# darwin-water-temp-module.net
KiCad netlist of a schematic drawn in EAGLE
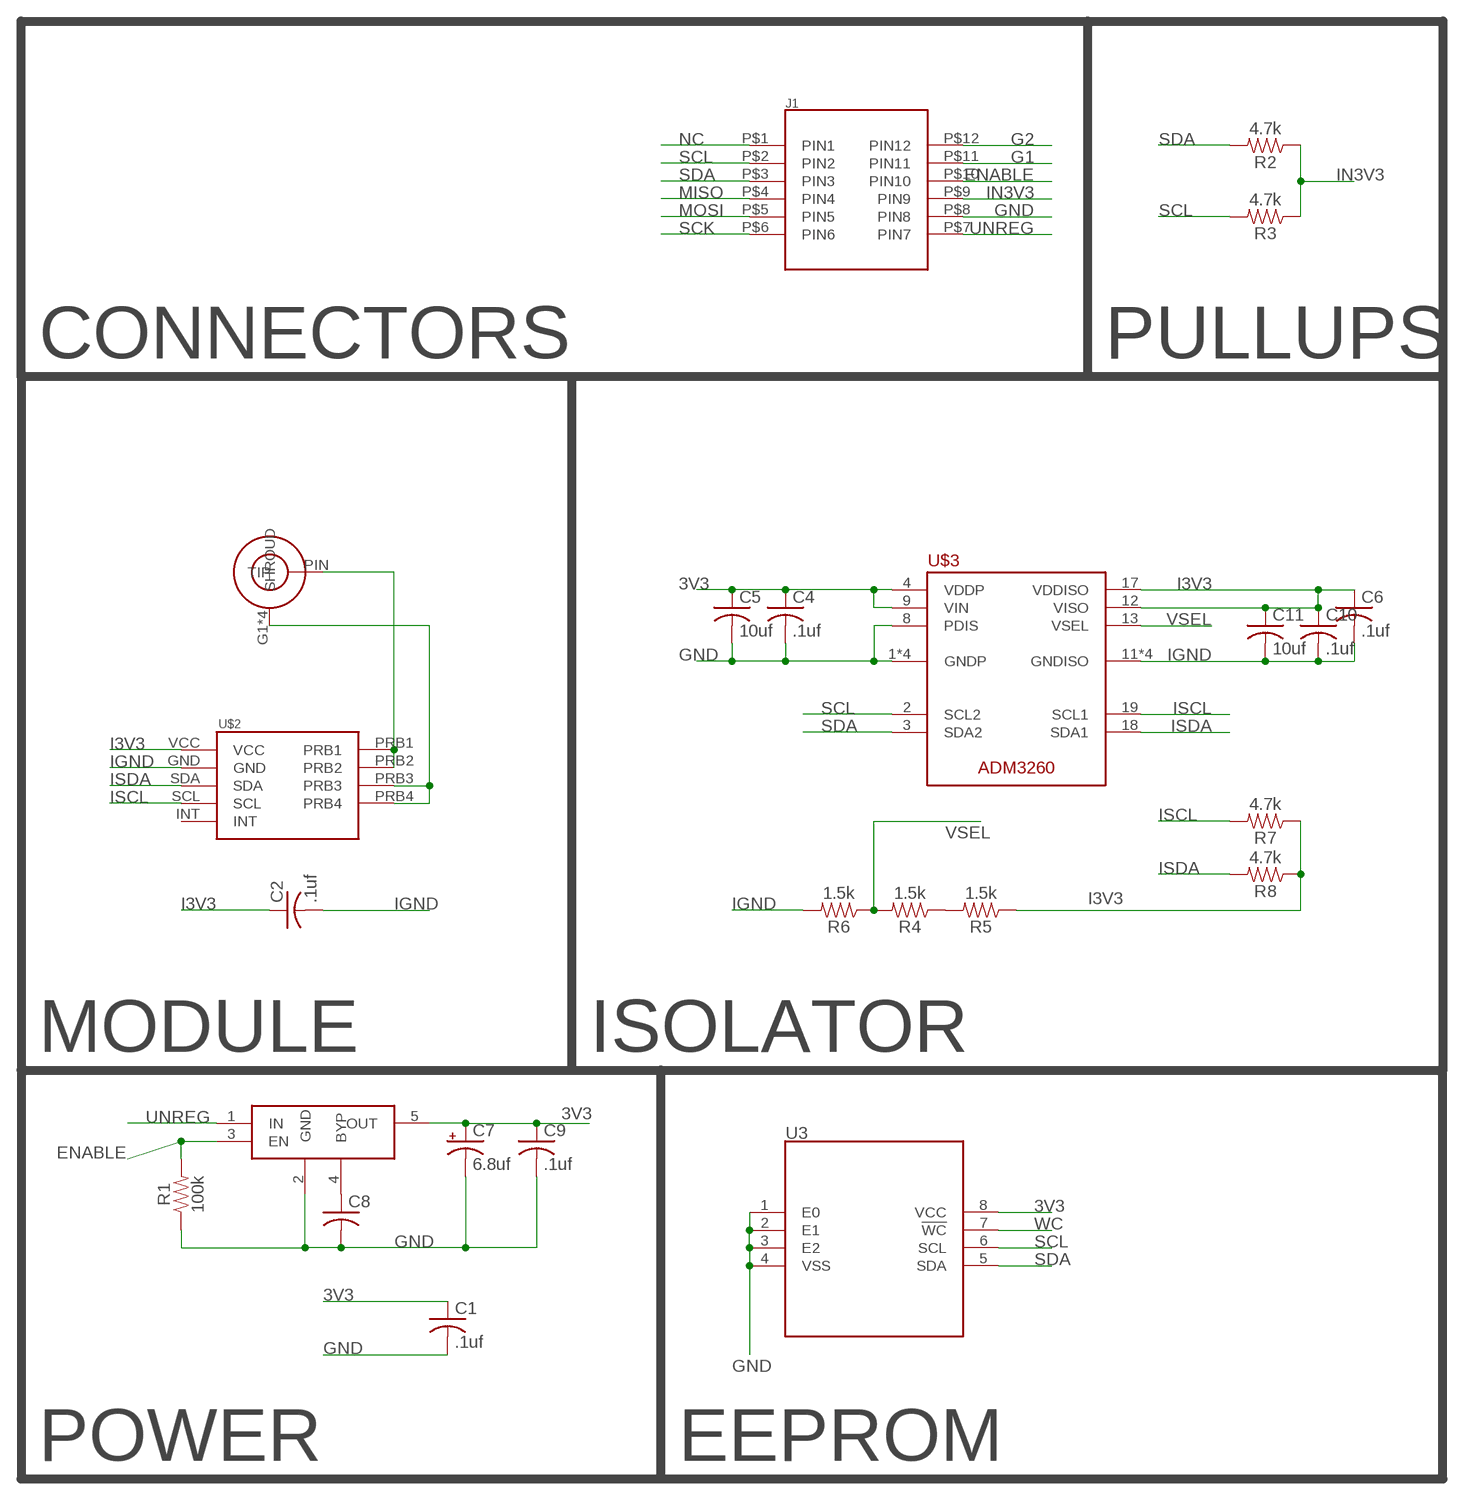
[diagram p0: schematic, sheet 1]

(export (version "E")
  (design (tool "Eeschema 10.0.6"))
  (components
    (comp (ref "C1")
      (value ".1uf")
      (footprint "eagle-import:C0603K")
      (libsource (lib "eagle-import") (part "C-USC0603K"))
    )
    (comp (ref "C2")
      (value ".1uf")
      (footprint "eagle-import:C0603K")
      (libsource (lib "eagle-import") (part "C-USC0603K"))
    )
    (comp (ref "C4")
      (value ".1uf")
      (footprint "eagle-import:C0603K")
      (libsource (lib "eagle-import") (part "C-USC0603K"))
    )
    (comp (ref "C5")
      (value "10uf")
      (footprint "eagle-import:C0603K")
      (libsource (lib "eagle-import") (part "C-USC0603K"))
    )
    (comp (ref "C6")
      (value ".1uf")
      (footprint "eagle-import:C0603K")
      (libsource (lib "eagle-import") (part "C-USC0603K"))
    )
    (comp (ref "C7")
      (value "6.8uf")
      (footprint "eagle-import:A_3216-18R")
      (libsource (lib "eagle-import") (part "CPOL-USA/3216-18R"))
    )
    (comp (ref "C8")
      (value "C-USC0603K")
      (footprint "eagle-import:C0603K")
      (libsource (lib "eagle-import") (part "C-USC0603K"))
    )
    (comp (ref "C9")
      (value ".1uf")
      (footprint "eagle-import:C0603K")
      (libsource (lib "eagle-import") (part "C-USC0603K"))
    )
    (comp (ref "C10")
      (value ".1uf")
      (footprint "eagle-import:C0603K")
      (libsource (lib "eagle-import") (part "C-USC0603K"))
    )
    (comp (ref "C11")
      (value "10uf")
      (footprint "eagle-import:C0603K")
      (libsource (lib "eagle-import") (part "C-USC0603K"))
    )
    (comp (ref "J1")
      (value "2X6-HEADERS")
      (footprint "eagle-import:M20-7810645")
      (libsource (lib "eagle-import") (part "2X6-HEADERS"))
    )
    (comp (ref "R1")
      (value "100k")
      (footprint "eagle-import:0603")
      (libsource (lib "eagle-import") (part "100KOHM-0603-1/10W-1%"))
    )
    (comp (ref "R2")
      (value "4.7k")
      (footprint "eagle-import:0603")
      (libsource (lib "eagle-import") (part "100KOHM-0603-1/10W-1%"))
    )
    (comp (ref "R3")
      (value "4.7k")
      (footprint "eagle-import:0603")
      (libsource (lib "eagle-import") (part "100KOHM-0603-1/10W-1%"))
    )
    (comp (ref "R4")
      (value "1.5k")
      (footprint "eagle-import:0603")
      (libsource (lib "eagle-import") (part "100KOHM-0603-1/10W-1%"))
    )
    (comp (ref "R5")
      (value "1.5k")
      (footprint "eagle-import:0603")
      (libsource (lib "eagle-import") (part "100KOHM-0603-1/10W-1%"))
    )
    (comp (ref "R6")
      (value "1.5k")
      (footprint "eagle-import:0603")
      (libsource (lib "eagle-import") (part "100KOHM-0603-1/10W-1%"))
    )
    (comp (ref "R7")
      (value "4.7k")
      (footprint "eagle-import:0603")
      (libsource (lib "eagle-import") (part "100KOHM-0603-1/10W-1%"))
    )
    (comp (ref "R8")
      (value "4.7k")
      (footprint "eagle-import:0603")
      (libsource (lib "eagle-import") (part "100KOHM-0603-1/10W-1%"))
    )
    (comp (ref "U$1")
      (value "5-1814832-1")
      (footprint "eagle-import:5-1814832-1")
      (libsource (lib "eagle-import") (part "5-1814832-1"))
    )
    (comp (ref "U$2")
      (value "ATLAS12P")
      (footprint "eagle-import:ATLAS-12P")
      (libsource (lib "eagle-import") (part "ATLAS12P"))
    )
    (comp (ref "U$3")
      (value "ADM3260")
      (footprint "eagle-import:SOP65P780X200-20")
      (libsource (lib "eagle-import") (part "ADM3260"))
    )
    (comp (ref "U$4")
      (value "MIC5219-3.3YM5-TR")
      (footprint "eagle-import:SOT95P280X145-5")
      (libsource (lib "eagle-import") (part "MIC5219-3.3YM5-TR"))
    )
    (comp (ref "U3")
      (value "M24C02-WMN6TP")
      (footprint "eagle-import:SOIC127P600X175-8")
      (libsource (lib "eagle-import") (part "M24C02-WMN6TP"))
    )
  )
  (nets
    (net (code "1") (name "/3V3") (class "Default")
      (node (ref "C1") (pin "1") (pinfunction "1_1") (pintype "passive"))
      (node (ref "C4") (pin "1") (pinfunction "1_1") (pintype "passive"))
      (node (ref "C5") (pin "1") (pinfunction "1_1") (pintype "passive"))
      (node (ref "C7") (pin "+") (pinfunction "+_+") (pintype "passive"))
      (node (ref "C9") (pin "1") (pinfunction "1_1") (pintype "passive"))
      (node (ref "U$3") (pin "4") (pinfunction "VDDP_4") (pintype "bidirectional"))
      (node (ref "U$3") (pin "9") (pinfunction "VIN_9") (pintype "bidirectional"))
      (node (ref "U$4") (pin "5") (pinfunction "OUT_5") (pintype "bidirectional"))
      (node (ref "U3") (pin "8") (pinfunction "VCC_8") (pintype "bidirectional"))
    )
    (net (code "2") (name "/ENABLE") (class "Default")
      (node (ref "J1") (pin "P$10") (pinfunction "PIN10_P$10") (pintype "bidirectional"))
      (node (ref "R1") (pin "2") (pinfunction "2_2") (pintype "passive"))
      (node (ref "U$4") (pin "3") (pinfunction "EN_3") (pintype "bidirectional"))
    )
    (net (code "3") (name "/G1") (class "Default")
      (node (ref "J1") (pin "P$11") (pinfunction "PIN11_P$11") (pintype "bidirectional"))
    )
    (net (code "4") (name "/G2") (class "Default")
      (node (ref "J1") (pin "P$12") (pinfunction "PIN12_P$12") (pintype "bidirectional"))
    )
    (net (code "5") (name "/GND") (class "Default")
      (node (ref "C1") (pin "2") (pinfunction "2_2") (pintype "passive"))
      (node (ref "C4") (pin "2") (pinfunction "2_2") (pintype "passive"))
      (node (ref "C5") (pin "2") (pinfunction "2_2") (pintype "passive"))
      (node (ref "C7") (pin "-") (pinfunction "-_-") (pintype "passive"))
      (node (ref "C8") (pin "2") (pinfunction "2_2") (pintype "passive"))
      (node (ref "C9") (pin "2") (pinfunction "2_2") (pintype "passive"))
      (node (ref "J1") (pin "P$8") (pinfunction "PIN8_P$8") (pintype "bidirectional"))
      (node (ref "R1") (pin "1") (pinfunction "1_1") (pintype "passive"))
      (node (ref "U$3") (pin "1") (pinfunction "GNDP_1") (pintype "bidirectional"))
      (node (ref "U$3") (pin "10") (pinfunction "GNDP_10") (pintype "bidirectional"))
      (node (ref "U$3") (pin "5") (pinfunction "GNDP_5") (pintype "bidirectional"))
      (node (ref "U$3") (pin "7") (pinfunction "GNDP_7") (pintype "bidirectional"))
      (node (ref "U$3") (pin "8") (pinfunction "PDIS_8") (pintype "bidirectional"))
      (node (ref "U$4") (pin "2") (pinfunction "GND_2") (pintype "bidirectional"))
      (node (ref "U3") (pin "1") (pinfunction "E0_1") (pintype "bidirectional"))
      (node (ref "U3") (pin "2") (pinfunction "E1_2") (pintype "bidirectional"))
      (node (ref "U3") (pin "3") (pinfunction "E2_3") (pintype "bidirectional"))
      (node (ref "U3") (pin "4") (pinfunction "VSS_4") (pintype "bidirectional"))
    )
    (net (code "6") (name "/I3V3") (class "Default")
      (node (ref "C10") (pin "1") (pinfunction "1_1") (pintype "passive"))
      (node (ref "C11") (pin "1") (pinfunction "1_1") (pintype "passive"))
      (node (ref "C2") (pin "1") (pinfunction "1_1") (pintype "passive"))
      (node (ref "C6") (pin "1") (pinfunction "1_1") (pintype "passive"))
      (node (ref "R5") (pin "1") (pinfunction "1_1") (pintype "passive"))
      (node (ref "R7") (pin "1") (pinfunction "1_1") (pintype "passive"))
      (node (ref "R8") (pin "1") (pinfunction "1_1") (pintype "passive"))
      (node (ref "U$2") (pin "VCC") (pinfunction "VCC_VCC") (pintype "bidirectional"))
      (node (ref "U$3") (pin "12") (pinfunction "VISO_12") (pintype "bidirectional"))
      (node (ref "U$3") (pin "17") (pinfunction "VDDISO_17") (pintype "bidirectional"))
    )
    (net (code "7") (name "/IGND") (class "Default")
      (node (ref "C10") (pin "2") (pinfunction "2_2") (pintype "passive"))
      (node (ref "C11") (pin "2") (pinfunction "2_2") (pintype "passive"))
      (node (ref "C2") (pin "2") (pinfunction "2_2") (pintype "passive"))
      (node (ref "C6") (pin "2") (pinfunction "2_2") (pintype "passive"))
      (node (ref "R6") (pin "2") (pinfunction "2_2") (pintype "passive"))
      (node (ref "U$2") (pin "GND") (pinfunction "GND_GND") (pintype "bidirectional"))
      (node (ref "U$3") (pin "11") (pinfunction "GNDISO_11") (pintype "bidirectional"))
      (node (ref "U$3") (pin "14") (pinfunction "GNDISO_14") (pintype "bidirectional"))
      (node (ref "U$3") (pin "16") (pinfunction "GNDISO_16") (pintype "bidirectional"))
      (node (ref "U$3") (pin "20") (pinfunction "GNDISO_20") (pintype "bidirectional"))
    )
    (net (code "8") (name "/IN3V3") (class "Default")
      (node (ref "J1") (pin "P$9") (pinfunction "PIN9_P$9") (pintype "bidirectional"))
      (node (ref "R2") (pin "1") (pinfunction "1_1") (pintype "passive"))
      (node (ref "R3") (pin "1") (pinfunction "1_1") (pintype "passive"))
    )
    (net (code "9") (name "/ISCL") (class "Default")
      (node (ref "R7") (pin "2") (pinfunction "2_2") (pintype "passive"))
      (node (ref "U$2") (pin "SCL") (pinfunction "SCL_SCL") (pintype "bidirectional"))
      (node (ref "U$3") (pin "19") (pinfunction "SCL1_19") (pintype "bidirectional"))
    )
    (net (code "10") (name "/ISDA") (class "Default")
      (node (ref "R8") (pin "2") (pinfunction "2_2") (pintype "passive"))
      (node (ref "U$2") (pin "SDA") (pinfunction "SDA_SDA") (pintype "bidirectional"))
      (node (ref "U$3") (pin "18") (pinfunction "SDA1_18") (pintype "bidirectional"))
    )
    (net (code "11") (name "/MISO") (class "Default")
      (node (ref "J1") (pin "P$4") (pinfunction "PIN4_P$4") (pintype "bidirectional"))
    )
    (net (code "12") (name "/MOSI") (class "Default")
      (node (ref "J1") (pin "P$5") (pinfunction "PIN5_P$5") (pintype "bidirectional"))
    )
    (net (code "13") (name "/NC") (class "Default")
      (node (ref "J1") (pin "P$1") (pinfunction "PIN1_P$1") (pintype "bidirectional"))
    )
    (net (code "14") (name "/SCK") (class "Default")
      (node (ref "J1") (pin "P$6") (pinfunction "PIN6_P$6") (pintype "bidirectional"))
    )
    (net (code "15") (name "/SCL") (class "Default")
      (node (ref "J1") (pin "P$2") (pinfunction "PIN2_P$2") (pintype "bidirectional"))
      (node (ref "R3") (pin "2") (pinfunction "2_2") (pintype "passive"))
      (node (ref "U$3") (pin "2") (pinfunction "SCL2_2") (pintype "bidirectional"))
      (node (ref "U3") (pin "6") (pinfunction "SCL_6") (pintype "bidirectional"))
    )
    (net (code "16") (name "/SDA") (class "Default")
      (node (ref "J1") (pin "P$3") (pinfunction "PIN3_P$3") (pintype "bidirectional"))
      (node (ref "R2") (pin "2") (pinfunction "2_2") (pintype "passive"))
      (node (ref "U$3") (pin "3") (pinfunction "SDA2_3") (pintype "bidirectional"))
      (node (ref "U3") (pin "5") (pinfunction "SDA_5") (pintype "bidirectional"))
    )
    (net (code "17") (name "/UNREG") (class "Default")
      (node (ref "J1") (pin "P$7") (pinfunction "PIN7_P$7") (pintype "bidirectional"))
      (node (ref "U$4") (pin "1") (pinfunction "IN_1") (pintype "bidirectional"))
    )
    (net (code "18") (name "/VSEL") (class "Default")
      (node (ref "R4") (pin "2") (pinfunction "2_2") (pintype "passive"))
      (node (ref "R6") (pin "1") (pinfunction "1_1") (pintype "passive"))
      (node (ref "U$3") (pin "13") (pinfunction "VSEL_13") (pintype "bidirectional"))
    )
    (net (code "19") (name "/WC") (class "Default")
      (node (ref "U3") (pin "7") (pinfunction "~{WC}_7") (pintype "bidirectional"))
    )
    (net (code "20") (name "Net-(R4-Pad1)") (class "Default")
      (node (ref "R4") (pin "1") (pinfunction "1_1") (pintype "passive"))
      (node (ref "R5") (pin "2") (pinfunction "2_2") (pintype "passive"))
    )
    (net (code "21") (name "Net-(U$1-SHROUD-PadG1)") (class "Default")
      (node (ref "U$1") (pin "G1") (pinfunction "SHROUD_G1") (pintype "bidirectional"))
      (node (ref "U$1") (pin "G2") (pinfunction "SHROUD_G2") (pintype "bidirectional"))
      (node (ref "U$1") (pin "G3") (pinfunction "SHROUD_G3") (pintype "bidirectional"))
      (node (ref "U$1") (pin "G4") (pinfunction "SHROUD_G4") (pintype "bidirectional"))
      (node (ref "U$2") (pin "PRB3") (pinfunction "PRB3_PRB3") (pintype "bidirectional"))
      (node (ref "U$2") (pin "PRB4") (pinfunction "PRB4_PRB4") (pintype "bidirectional"))
    )
    (net (code "22") (name "Net-(U$1-TIP)") (class "Default")
      (node (ref "U$1") (pin "PIN") (pinfunction "TIP_PIN") (pintype "bidirectional"))
      (node (ref "U$2") (pin "PRB1") (pinfunction "PRB1_PRB1") (pintype "bidirectional"))
      (node (ref "U$2") (pin "PRB2") (pinfunction "PRB2_PRB2") (pintype "bidirectional"))
    )
    (net (code "23") (name "Net-(U$4-BYP)") (class "Default")
      (node (ref "C8") (pin "1") (pinfunction "1_1") (pintype "passive"))
      (node (ref "U$4") (pin "4") (pinfunction "BYP_4") (pintype "bidirectional"))
    )
    (net (code "24") (name "unconnected-(U$2-PadINT)") (class "Default")
      (node (ref "U$2") (pin "INT") (pinfunction "INT_INT") (pintype "bidirectional"))
    )
  )
)
